# USB-Hub-Schematic.net
KiCad netlist of a schematic drawn in EasyEDA
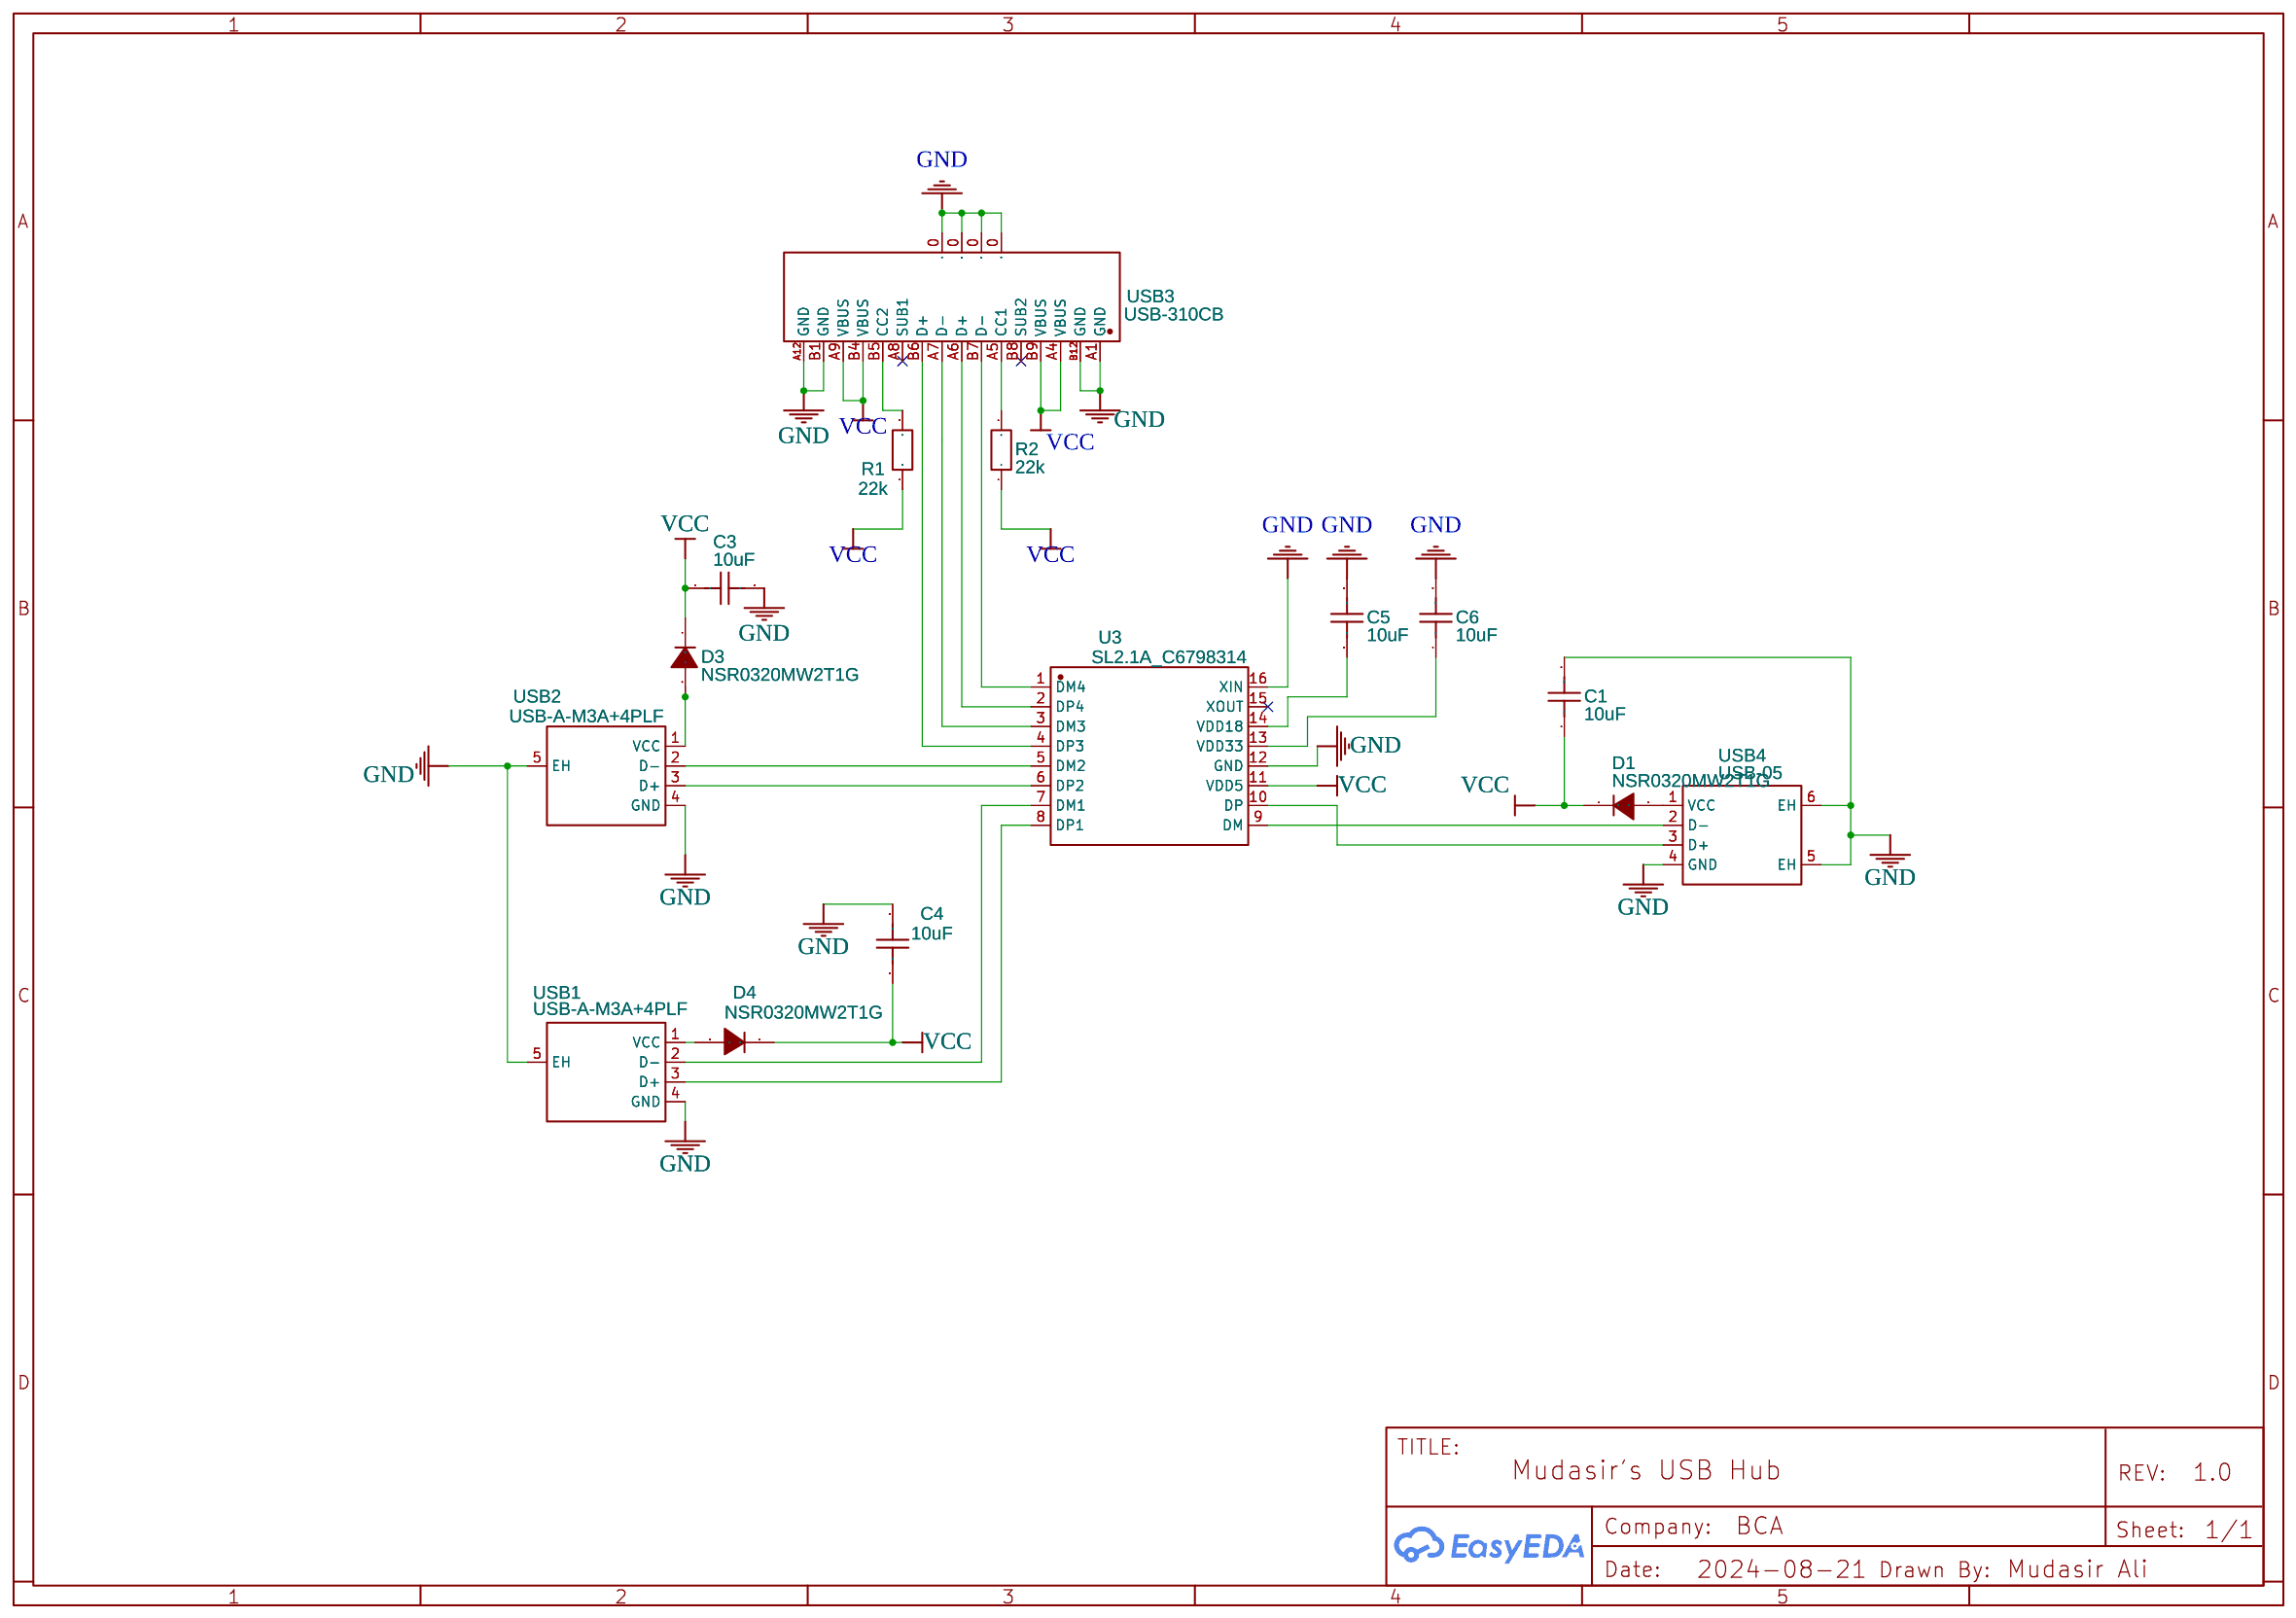
[diagram p0: schematic sheet]

(export (version "E")
  (design (tool "Eeschema 10.0.6"))
  (components
    (comp (ref "C1")
      (value "10uF")
      (fields
        (field (name "Manufacturer Part") "CL10A106KP8NNNC")
        (field (name "Manufacturer") "SAMSUNG(三星)")
      )
      (libsource (lib "") (part "CL10A106KP8NNNC"))
    )
    (comp (ref "C3")
      (value "10uF")
      (fields
        (field (name "Manufacturer Part") "CL10A106KP8NNNC")
        (field (name "Manufacturer") "SAMSUNG(三星)")
      )
      (libsource (lib "") (part "CL10A106KP8NNNC_1"))
    )
    (comp (ref "C4")
      (value "10uF")
      (fields
        (field (name "Manufacturer Part") "CL10A106KP8NNNC")
        (field (name "Manufacturer") "SAMSUNG(三星)")
      )
      (libsource (lib "") (part "CL10A106KP8NNNC"))
    )
    (comp (ref "C5")
      (value "10uF")
      (fields
        (field (name "Manufacturer Part") "CL10A106KP8NNNC")
        (field (name "Manufacturer") "SAMSUNG(三星)")
      )
      (libsource (lib "") (part "CL10A106KP8NNNC"))
    )
    (comp (ref "C6")
      (value "10uF")
      (fields
        (field (name "Manufacturer Part") "CL10A106KP8NNNC")
        (field (name "Manufacturer") "SAMSUNG(三星)")
      )
      (libsource (lib "") (part "CL10A106KP8NNNC"))
    )
    (comp (ref "D1")
      (value "NSR0320MW2T1G")
      (fields (field (name "Manufacturer") "onsemi(安森美)"))
      (libsource (lib "") (part "NSR0320MW2T1G"))
    )
    (comp (ref "D3")
      (value "NSR0320MW2T1G")
      (fields (field (name "Manufacturer") "onsemi(安森美)"))
      (libsource (lib "") (part "NSR0320MW2T1G_1"))
    )
    (comp (ref "D4")
      (value "NSR0320MW2T1G")
      (fields (field (name "Manufacturer") "onsemi(安森美)"))
      (libsource (lib "") (part "NSR0320MW2T1G_2"))
    )
    (comp (ref "R1") (value "22k") (libsource (lib "") (part "R_0603_EU")))
    (comp (ref "R2") (value "22k") (libsource (lib "") (part "R_0603_EU")))
    (comp (ref "U3")
      (value "SL2.1A_C6798314")
      (fields (field (name "Manufacturer Part") "SL2.1A") (field (name "Manufacturer") "CoreChips(和芯润德)"))
      (libsource (lib "") (part "SL2.1A_C6798314"))
    )
    (comp (ref "USB1")
      (value "USB-A-M3A+4PLF")
      (fields (field (name "Manufacturer") "JINJIA(金佳)"))
      (libsource (lib "") (part "USB-A-M3A+4PLF"))
    )
    (comp (ref "USB2")
      (value "USB-A-M3A+4PLF")
      (fields (field (name "Manufacturer") "JINJIA(金佳)"))
      (libsource (lib "") (part "USB-A-M3A+4PLF"))
    )
    (comp (ref "USB3")
      (value "USB-310CB")
      (fields (field (name "Manufacturer") "HOOYA(皓宇电子)"))
      (libsource (lib "") (part "USB-310CB"))
    )
    (comp (ref "USB4")
      (value "USB-05")
      (fields (field (name "Manufacturer") "SOFNG(硕方)"))
      (libsource (lib "") (part "USB-05"))
    )
  )
  (nets
    (net (code "1") (name "GND") (class "Default")
      (node (ref "C1") (pin "2") (pinfunction "2_2") (pintype "unspecified"))
      (node (ref "C3") (pin "2") (pinfunction "2_2") (pintype "unspecified"))
      (node (ref "C4") (pin "2") (pinfunction "2_2") (pintype "unspecified"))
      (node (ref "C5") (pin "2") (pinfunction "2_2") (pintype "unspecified"))
      (node (ref "C6") (pin "2") (pinfunction "2_2") (pintype "unspecified"))
      (node (ref "U3") (pin "12") (pinfunction "GND_12") (pintype "unspecified"))
      (node (ref "U3") (pin "16") (pinfunction "XIN_16") (pintype "unspecified"))
      (node (ref "USB1") (pin "4") (pinfunction "GND_4") (pintype "input"))
      (node (ref "USB1") (pin "5") (pinfunction "EH_5") (pintype "unspecified"))
      (node (ref "USB2") (pin "4") (pinfunction "GND_4") (pintype "input"))
      (node (ref "USB2") (pin "5") (pinfunction "EH_5") (pintype "unspecified"))
      (node (ref "USB3") (pin "0") (pinfunction "0_0") (pintype "unspecified"))
      (node (ref "USB3") (pin "A1") (pinfunction "GND_A1") (pintype "unspecified"))
      (node (ref "USB3") (pin "A12") (pinfunction "GND_A12") (pintype "unspecified"))
      (node (ref "USB3") (pin "B1") (pinfunction "GND_B1") (pintype "unspecified"))
      (node (ref "USB3") (pin "B12") (pinfunction "GND_B12") (pintype "unspecified"))
      (node (ref "USB4") (pin "4") (pinfunction "GND_4") (pintype "input"))
      (node (ref "USB4") (pin "5") (pinfunction "EH_5") (pintype "unspecified"))
      (node (ref "USB4") (pin "6") (pinfunction "EH_6") (pintype "unspecified"))
    )
    (net (code "2") (name "Net-(D1-A)") (class "Default")
      (node (ref "D1") (pin "2") (pinfunction "A_2") (pintype "unspecified"))
      (node (ref "USB4") (pin "1") (pinfunction "VCC_1") (pintype "input"))
    )
    (net (code "3") (name "Net-(D3-A)") (class "Default")
      (node (ref "D3") (pin "2") (pinfunction "A_2") (pintype "unspecified"))
      (node (ref "USB2") (pin "1") (pinfunction "VCC_1") (pintype "input"))
    )
    (net (code "4") (name "Net-(D4-A)") (class "Default")
      (node (ref "D4") (pin "2") (pinfunction "A_2") (pintype "unspecified"))
      (node (ref "USB1") (pin "1") (pinfunction "VCC_1") (pintype "input"))
    )
    (net (code "5") (name "Net-(U3-DM)") (class "Default")
      (node (ref "U3") (pin "9") (pinfunction "DM_9") (pintype "unspecified"))
      (node (ref "USB4") (pin "2") (pinfunction "D-_2") (pintype "input"))
    )
    (net (code "6") (name "Net-(U3-DM1)") (class "Default")
      (node (ref "U3") (pin "7") (pinfunction "DM1_7") (pintype "unspecified"))
      (node (ref "USB1") (pin "2") (pinfunction "D-_2") (pintype "input"))
    )
    (net (code "7") (name "Net-(U3-DM2)") (class "Default")
      (node (ref "U3") (pin "5") (pinfunction "DM2_5") (pintype "unspecified"))
      (node (ref "USB2") (pin "2") (pinfunction "D-_2") (pintype "input"))
    )
    (net (code "8") (name "Net-(U3-DM3)") (class "Default")
      (node (ref "U3") (pin "3") (pinfunction "DM3_3") (pintype "unspecified"))
      (node (ref "USB3") (pin "A7") (pinfunction "D-_A7") (pintype "unspecified"))
    )
    (net (code "9") (name "Net-(U3-DM4)") (class "Default")
      (node (ref "U3") (pin "1") (pinfunction "DM4_1") (pintype "unspecified"))
      (node (ref "USB3") (pin "B7") (pinfunction "D-_B7") (pintype "unspecified"))
    )
    (net (code "10") (name "Net-(U3-DP)") (class "Default")
      (node (ref "U3") (pin "10") (pinfunction "DP_10") (pintype "unspecified"))
      (node (ref "USB4") (pin "3") (pinfunction "D+_3") (pintype "input"))
    )
    (net (code "11") (name "Net-(U3-DP1)") (class "Default")
      (node (ref "U3") (pin "8") (pinfunction "DP1_8") (pintype "unspecified"))
      (node (ref "USB1") (pin "3") (pinfunction "D+_3") (pintype "input"))
    )
    (net (code "12") (name "Net-(U3-DP2)") (class "Default")
      (node (ref "U3") (pin "6") (pinfunction "DP2_6") (pintype "unspecified"))
      (node (ref "USB2") (pin "3") (pinfunction "D+_3") (pintype "input"))
    )
    (net (code "13") (name "Net-(U3-DP3)") (class "Default")
      (node (ref "U3") (pin "4") (pinfunction "DP3_4") (pintype "unspecified"))
      (node (ref "USB3") (pin "B6") (pinfunction "D+_B6") (pintype "unspecified"))
    )
    (net (code "14") (name "Net-(U3-DP4)") (class "Default")
      (node (ref "U3") (pin "2") (pinfunction "DP4_2") (pintype "unspecified"))
      (node (ref "USB3") (pin "A6") (pinfunction "D+_A6") (pintype "unspecified"))
    )
    (net (code "15") (name "Net-(U3-VDD18)") (class "Default")
      (node (ref "C5") (pin "1") (pinfunction "1_1") (pintype "unspecified"))
      (node (ref "U3") (pin "14") (pinfunction "VDD18_14") (pintype "unspecified"))
    )
    (net (code "16") (name "Net-(U3-VDD33)") (class "Default")
      (node (ref "C6") (pin "1") (pinfunction "1_1") (pintype "unspecified"))
      (node (ref "U3") (pin "13") (pinfunction "VDD33_13") (pintype "unspecified"))
    )
    (net (code "17") (name "Net-(USB3-CC1)") (class "Default")
      (node (ref "R2") (pin "2") (pinfunction "2_2") (pintype "unspecified"))
      (node (ref "USB3") (pin "A5") (pinfunction "CC1_A5") (pintype "unspecified"))
    )
    (net (code "18") (name "Net-(USB3-CC2)") (class "Default")
      (node (ref "R1") (pin "2") (pinfunction "2_2") (pintype "unspecified"))
      (node (ref "USB3") (pin "B5") (pinfunction "CC2_B5") (pintype "unspecified"))
    )
    (net (code "19") (name "VCC") (class "Default")
      (node (ref "C1") (pin "1") (pinfunction "1_1") (pintype "unspecified"))
      (node (ref "C3") (pin "1") (pinfunction "1_1") (pintype "unspecified"))
      (node (ref "C4") (pin "1") (pinfunction "1_1") (pintype "unspecified"))
      (node (ref "D1") (pin "1") (pinfunction "C_1") (pintype "unspecified"))
      (node (ref "D3") (pin "1") (pinfunction "C_1") (pintype "unspecified"))
      (node (ref "D4") (pin "1") (pinfunction "C_1") (pintype "unspecified"))
      (node (ref "R1") (pin "1") (pinfunction "1_1") (pintype "unspecified"))
      (node (ref "R2") (pin "1") (pinfunction "1_1") (pintype "unspecified"))
      (node (ref "U3") (pin "11") (pinfunction "VDD5_11") (pintype "unspecified"))
      (node (ref "USB3") (pin "A4") (pinfunction "VBUS_A4") (pintype "unspecified"))
      (node (ref "USB3") (pin "A9") (pinfunction "VBUS_A9") (pintype "unspecified"))
      (node (ref "USB3") (pin "B4") (pinfunction "VBUS_B4") (pintype "unspecified"))
      (node (ref "USB3") (pin "B9") (pinfunction "VBUS_B9") (pintype "unspecified"))
    )
    (net (code "20") (name "unconnected-(U3-XOUT-Pad15)") (class "Default")
      (node (ref "U3") (pin "15") (pinfunction "XOUT_15") (pintype "unspecified+no_connect"))
    )
    (net (code "21") (name "unconnected-(USB3-SUB1-PadA8)") (class "Default")
      (node (ref "USB3") (pin "A8") (pinfunction "SUB1_A8") (pintype "unspecified+no_connect"))
    )
    (net (code "22") (name "unconnected-(USB3-SUB2-PadB8)") (class "Default")
      (node (ref "USB3") (pin "B8") (pinfunction "SUB2_B8") (pintype "unspecified+no_connect"))
    )
  )
)
